# th.net
KiCad netlist of a schematic drawn in EAGLE
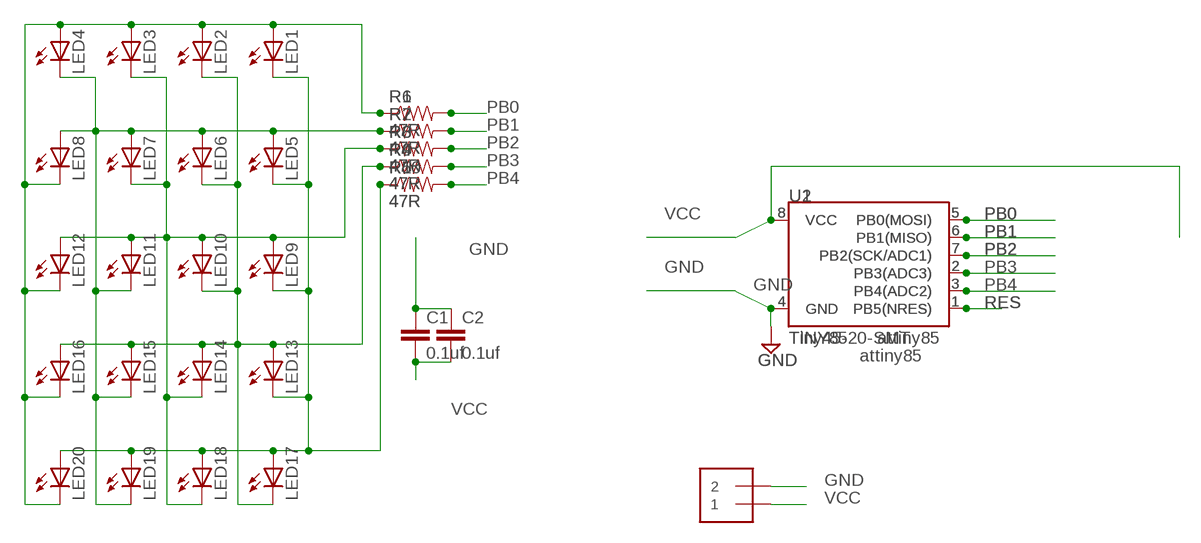
[diagram p0: schematic, sheet 1]

(export (version "E")
  (design (tool "Eeschema 10.0.6"))
  (components
    (comp (ref "C1")
      (value "0.1uf")
      (footprint "eagle-import:0603-CAP")
      (libsource (lib "eagle-import") (part "CAP0603-CAP"))
    )
    (comp (ref "C2")
      (value "0.1uf")
      (footprint "eagle-import:CAP-PTH-SMALL-KIT")
      (libsource (lib "eagle-import") (part "CAPKIT"))
    )
    (comp (ref "J1")
      (value "1X2-3.5MM")
      (footprint "eagle-import:1X2-3.5MM")
      (libsource (lib "eagle-import") (part "1X2-3.5MM"))
    )
    (comp (ref "LED1")
      (value "LED3MM")
      (footprint "eagle-import:LED3MM")
      (libsource (lib "eagle-import") (part "LED3MM"))
    )
    (comp (ref "LED2")
      (value "LED3MM")
      (footprint "eagle-import:LED3MM")
      (libsource (lib "eagle-import") (part "LED3MM"))
    )
    (comp (ref "LED3")
      (value "LED3MM")
      (footprint "eagle-import:LED3MM")
      (libsource (lib "eagle-import") (part "LED3MM"))
    )
    (comp (ref "LED4")
      (value "LED3MM")
      (footprint "eagle-import:LED3MM")
      (libsource (lib "eagle-import") (part "LED3MM"))
    )
    (comp (ref "LED5")
      (value "LED3MM")
      (footprint "eagle-import:LED3MM")
      (libsource (lib "eagle-import") (part "LED3MM"))
    )
    (comp (ref "LED6")
      (value "LED3MM")
      (footprint "eagle-import:LED3MM")
      (libsource (lib "eagle-import") (part "LED3MM"))
    )
    (comp (ref "LED7")
      (value "LED3MM")
      (footprint "eagle-import:LED3MM")
      (libsource (lib "eagle-import") (part "LED3MM"))
    )
    (comp (ref "LED8")
      (value "LED3MM")
      (footprint "eagle-import:LED3MM")
      (libsource (lib "eagle-import") (part "LED3MM"))
    )
    (comp (ref "LED9")
      (value "LED3MM")
      (footprint "eagle-import:LED3MM")
      (libsource (lib "eagle-import") (part "LED3MM"))
    )
    (comp (ref "LED10")
      (value "LED3MM")
      (footprint "eagle-import:LED3MM")
      (libsource (lib "eagle-import") (part "LED3MM"))
    )
    (comp (ref "LED11")
      (value "LED3MM")
      (footprint "eagle-import:LED3MM")
      (libsource (lib "eagle-import") (part "LED3MM"))
    )
    (comp (ref "LED12")
      (value "LED3MM")
      (footprint "eagle-import:LED3MM")
      (libsource (lib "eagle-import") (part "LED3MM"))
    )
    (comp (ref "LED13")
      (value "LED3MM")
      (footprint "eagle-import:LED3MM")
      (libsource (lib "eagle-import") (part "LED3MM"))
    )
    (comp (ref "LED14")
      (value "LED3MM")
      (footprint "eagle-import:LED3MM")
      (libsource (lib "eagle-import") (part "LED3MM"))
    )
    (comp (ref "LED15")
      (value "LED3MM")
      (footprint "eagle-import:LED3MM")
      (libsource (lib "eagle-import") (part "LED3MM"))
    )
    (comp (ref "LED16")
      (value "LED3MM")
      (footprint "eagle-import:LED3MM")
      (libsource (lib "eagle-import") (part "LED3MM"))
    )
    (comp (ref "LED17")
      (value "LED3MM")
      (footprint "eagle-import:LED3MM")
      (libsource (lib "eagle-import") (part "LED3MM"))
    )
    (comp (ref "LED18")
      (value "LED3MM")
      (footprint "eagle-import:LED3MM")
      (libsource (lib "eagle-import") (part "LED3MM"))
    )
    (comp (ref "LED19")
      (value "LED3MM")
      (footprint "eagle-import:LED3MM")
      (libsource (lib "eagle-import") (part "LED3MM"))
    )
    (comp (ref "LED20")
      (value "LED3MM")
      (footprint "eagle-import:LED3MM")
      (libsource (lib "eagle-import") (part "LED3MM"))
    )
    (comp (ref "R1")
      (value "47R")
      (footprint "eagle-import:AXIAL-0.3")
      (libsource (lib "eagle-import") (part "RESISTORAXIAL-0.3"))
    )
    (comp (ref "R2")
      (value "47R")
      (footprint "eagle-import:AXIAL-0.3")
      (libsource (lib "eagle-import") (part "RESISTORAXIAL-0.3"))
    )
    (comp (ref "R3")
      (value "47R")
      (footprint "eagle-import:AXIAL-0.3")
      (libsource (lib "eagle-import") (part "RESISTORAXIAL-0.3"))
    )
    (comp (ref "R4")
      (value "47R")
      (footprint "eagle-import:AXIAL-0.3")
      (libsource (lib "eagle-import") (part "RESISTORAXIAL-0.3"))
    )
    (comp (ref "R5")
      (value "47R")
      (footprint "eagle-import:AXIAL-0.3")
      (libsource (lib "eagle-import") (part "RESISTORAXIAL-0.3"))
    )
    (comp (ref "R6")
      (value "47R")
      (footprint "eagle-import:0603-RES")
      (libsource (lib "eagle-import") (part "RESISTOR0603-RES"))
    )
    (comp (ref "R7")
      (value "47R")
      (footprint "eagle-import:0603-RES")
      (libsource (lib "eagle-import") (part "RESISTOR0603-RES"))
    )
    (comp (ref "R8")
      (value "47R")
      (footprint "eagle-import:0603-RES")
      (libsource (lib "eagle-import") (part "RESISTOR0603-RES"))
    )
    (comp (ref "R9")
      (value "47R")
      (footprint "eagle-import:0603-RES")
      (libsource (lib "eagle-import") (part "RESISTOR0603-RES"))
    )
    (comp (ref "R10")
      (value "47R")
      (footprint "eagle-import:0603-RES")
      (libsource (lib "eagle-import") (part "RESISTOR0603-RES"))
    )
    (comp (ref "U1")
      (value "TINY85")
      (footprint "eagle-import:DIP08")
      (libsource (lib "eagle-import") (part "ATTINY45TINY45-20-DIP"))
    )
    (comp (ref "U2")
      (value "Tiny45-20-SMT")
      (footprint "eagle-import:SO08-EIAJ")
      (libsource (lib "eagle-import") (part "ATTINY45TINY45-20-SMT"))
    )
  )
  (nets
    (net (code "1") (name "/PB0") (class "Default")
      (node (ref "R1") (pin "P$2") (pinfunction "2_P$2") (pintype "passive"))
      (node (ref "R6") (pin "2") (pinfunction "2_2") (pintype "passive"))
      (node (ref "U1") (pin "5") (pinfunction "PB0(MOSI)_5") (pintype "bidirectional"))
      (node (ref "U2") (pin "5") (pinfunction "PB0(MOSI)_5") (pintype "bidirectional"))
    )
    (net (code "2") (name "/PB1") (class "Default")
      (node (ref "R2") (pin "P$2") (pinfunction "2_P$2") (pintype "passive"))
      (node (ref "R7") (pin "2") (pinfunction "2_2") (pintype "passive"))
      (node (ref "U1") (pin "6") (pinfunction "PB1(MISO)_6") (pintype "bidirectional"))
      (node (ref "U2") (pin "6") (pinfunction "PB1(MISO)_6") (pintype "bidirectional"))
    )
    (net (code "3") (name "/PB2") (class "Default")
      (node (ref "R3") (pin "P$2") (pinfunction "2_P$2") (pintype "passive"))
      (node (ref "R8") (pin "2") (pinfunction "2_2") (pintype "passive"))
      (node (ref "U1") (pin "7") (pinfunction "PB2(SCK/ADC1)_7") (pintype "bidirectional"))
      (node (ref "U2") (pin "7") (pinfunction "PB2(SCK/ADC1)_7") (pintype "bidirectional"))
    )
    (net (code "4") (name "/PB3") (class "Default")
      (node (ref "R4") (pin "P$2") (pinfunction "2_P$2") (pintype "passive"))
      (node (ref "R9") (pin "2") (pinfunction "2_2") (pintype "passive"))
      (node (ref "U1") (pin "2") (pinfunction "PB3(ADC3)_2") (pintype "bidirectional"))
      (node (ref "U2") (pin "2") (pinfunction "PB3(ADC3)_2") (pintype "bidirectional"))
    )
    (net (code "5") (name "/PB4") (class "Default")
      (node (ref "R10") (pin "2") (pinfunction "2_2") (pintype "passive"))
      (node (ref "R5") (pin "P$2") (pinfunction "2_P$2") (pintype "passive"))
      (node (ref "U1") (pin "3") (pinfunction "PB4(ADC2)_3") (pintype "bidirectional"))
      (node (ref "U2") (pin "3") (pinfunction "PB4(ADC2)_3") (pintype "bidirectional"))
    )
    (net (code "6") (name "/RES") (class "Default")
      (node (ref "U1") (pin "1") (pinfunction "PB5(NRES)_1") (pintype "bidirectional"))
      (node (ref "U2") (pin "1") (pinfunction "PB5(NRES)_1") (pintype "bidirectional"))
    )
    (net (code "7") (name "/VCC") (class "Default")
      (node (ref "C1") (pin "2") (pinfunction "2_2") (pintype "passive"))
      (node (ref "C2") (pin "2") (pinfunction "2_2") (pintype "passive"))
      (node (ref "J1") (pin "1") (pinfunction "1_1") (pintype "passive"))
      (node (ref "U1") (pin "8") (pinfunction "VCC_8") (pintype "bidirectional"))
      (node (ref "U2") (pin "8") (pinfunction "VCC_8") (pintype "bidirectional"))
    )
    (net (code "8") (name "GND") (class "Default")
      (node (ref "C1") (pin "1") (pinfunction "1_1") (pintype "passive"))
      (node (ref "C2") (pin "1") (pinfunction "1_1") (pintype "passive"))
      (node (ref "J1") (pin "2") (pinfunction "2_2") (pintype "passive"))
      (node (ref "U1") (pin "4") (pinfunction "GND_4") (pintype "bidirectional"))
      (node (ref "U2") (pin "4") (pinfunction "GND_4") (pintype "bidirectional"))
    )
    (net (code "9") (name "Net-(LED1-C)") (class "Default")
      (node (ref "LED1") (pin "K") (pinfunction "C_K") (pintype "passive"))
      (node (ref "LED13") (pin "K") (pinfunction "C_K") (pintype "passive"))
      (node (ref "LED17") (pin "A") (pinfunction "A_A") (pintype "passive"))
      (node (ref "LED18") (pin "A") (pinfunction "A_A") (pintype "passive"))
      (node (ref "LED19") (pin "A") (pinfunction "A_A") (pintype "passive"))
      (node (ref "LED20") (pin "A") (pinfunction "A_A") (pintype "passive"))
      (node (ref "LED5") (pin "K") (pinfunction "C_K") (pintype "passive"))
      (node (ref "LED9") (pin "K") (pinfunction "C_K") (pintype "passive"))
      (node (ref "R10") (pin "1") (pinfunction "1_1") (pintype "passive"))
      (node (ref "R5") (pin "P$1") (pinfunction "1_P$1") (pintype "passive"))
    )
    (net (code "10") (name "Net-(LED10-C)") (class "Default")
      (node (ref "LED10") (pin "K") (pinfunction "C_K") (pintype "passive"))
      (node (ref "LED13") (pin "A") (pinfunction "A_A") (pintype "passive"))
      (node (ref "LED14") (pin "A") (pinfunction "A_A") (pintype "passive"))
      (node (ref "LED15") (pin "A") (pinfunction "A_A") (pintype "passive"))
      (node (ref "LED16") (pin "A") (pinfunction "A_A") (pintype "passive"))
      (node (ref "LED17") (pin "K") (pinfunction "C_K") (pintype "passive"))
      (node (ref "LED2") (pin "K") (pinfunction "C_K") (pintype "passive"))
      (node (ref "LED6") (pin "K") (pinfunction "C_K") (pintype "passive"))
      (node (ref "R4") (pin "P$1") (pinfunction "1_P$1") (pintype "passive"))
      (node (ref "R9") (pin "1") (pinfunction "1_1") (pintype "passive"))
    )
    (net (code "11") (name "Net-(LED11-C)") (class "Default")
      (node (ref "LED11") (pin "K") (pinfunction "C_K") (pintype "passive"))
      (node (ref "LED15") (pin "K") (pinfunction "C_K") (pintype "passive"))
      (node (ref "LED19") (pin "K") (pinfunction "C_K") (pintype "passive"))
      (node (ref "LED4") (pin "K") (pinfunction "C_K") (pintype "passive"))
      (node (ref "LED5") (pin "A") (pinfunction "A_A") (pintype "passive"))
      (node (ref "LED6") (pin "A") (pinfunction "A_A") (pintype "passive"))
      (node (ref "LED7") (pin "A") (pinfunction "A_A") (pintype "passive"))
      (node (ref "LED8") (pin "A") (pinfunction "A_A") (pintype "passive"))
      (node (ref "R2") (pin "P$1") (pinfunction "1_P$1") (pintype "passive"))
      (node (ref "R7") (pin "1") (pinfunction "1_1") (pintype "passive"))
    )
    (net (code "12") (name "Net-(LED12-C)") (class "Default")
      (node (ref "LED1") (pin "A") (pinfunction "A_A") (pintype "passive"))
      (node (ref "LED12") (pin "K") (pinfunction "C_K") (pintype "passive"))
      (node (ref "LED16") (pin "K") (pinfunction "C_K") (pintype "passive"))
      (node (ref "LED2") (pin "A") (pinfunction "A_A") (pintype "passive"))
      (node (ref "LED20") (pin "K") (pinfunction "C_K") (pintype "passive"))
      (node (ref "LED3") (pin "A") (pinfunction "A_A") (pintype "passive"))
      (node (ref "LED4") (pin "A") (pinfunction "A_A") (pintype "passive"))
      (node (ref "LED8") (pin "K") (pinfunction "C_K") (pintype "passive"))
      (node (ref "R1") (pin "P$1") (pinfunction "1_P$1") (pintype "passive"))
      (node (ref "R6") (pin "1") (pinfunction "1_1") (pintype "passive"))
    )
    (net (code "13") (name "Net-(LED14-C)") (class "Default")
      (node (ref "LED10") (pin "A") (pinfunction "A_A") (pintype "passive"))
      (node (ref "LED11") (pin "A") (pinfunction "A_A") (pintype "passive"))
      (node (ref "LED12") (pin "A") (pinfunction "A_A") (pintype "passive"))
      (node (ref "LED14") (pin "K") (pinfunction "C_K") (pintype "passive"))
      (node (ref "LED18") (pin "K") (pinfunction "C_K") (pintype "passive"))
      (node (ref "LED3") (pin "K") (pinfunction "C_K") (pintype "passive"))
      (node (ref "LED7") (pin "K") (pinfunction "C_K") (pintype "passive"))
      (node (ref "LED9") (pin "A") (pinfunction "A_A") (pintype "passive"))
      (node (ref "R3") (pin "P$1") (pinfunction "1_P$1") (pintype "passive"))
      (node (ref "R8") (pin "1") (pinfunction "1_1") (pintype "passive"))
    )
  )
)
